# io.net
KiCad netlist of a schematic drawn in EAGLE
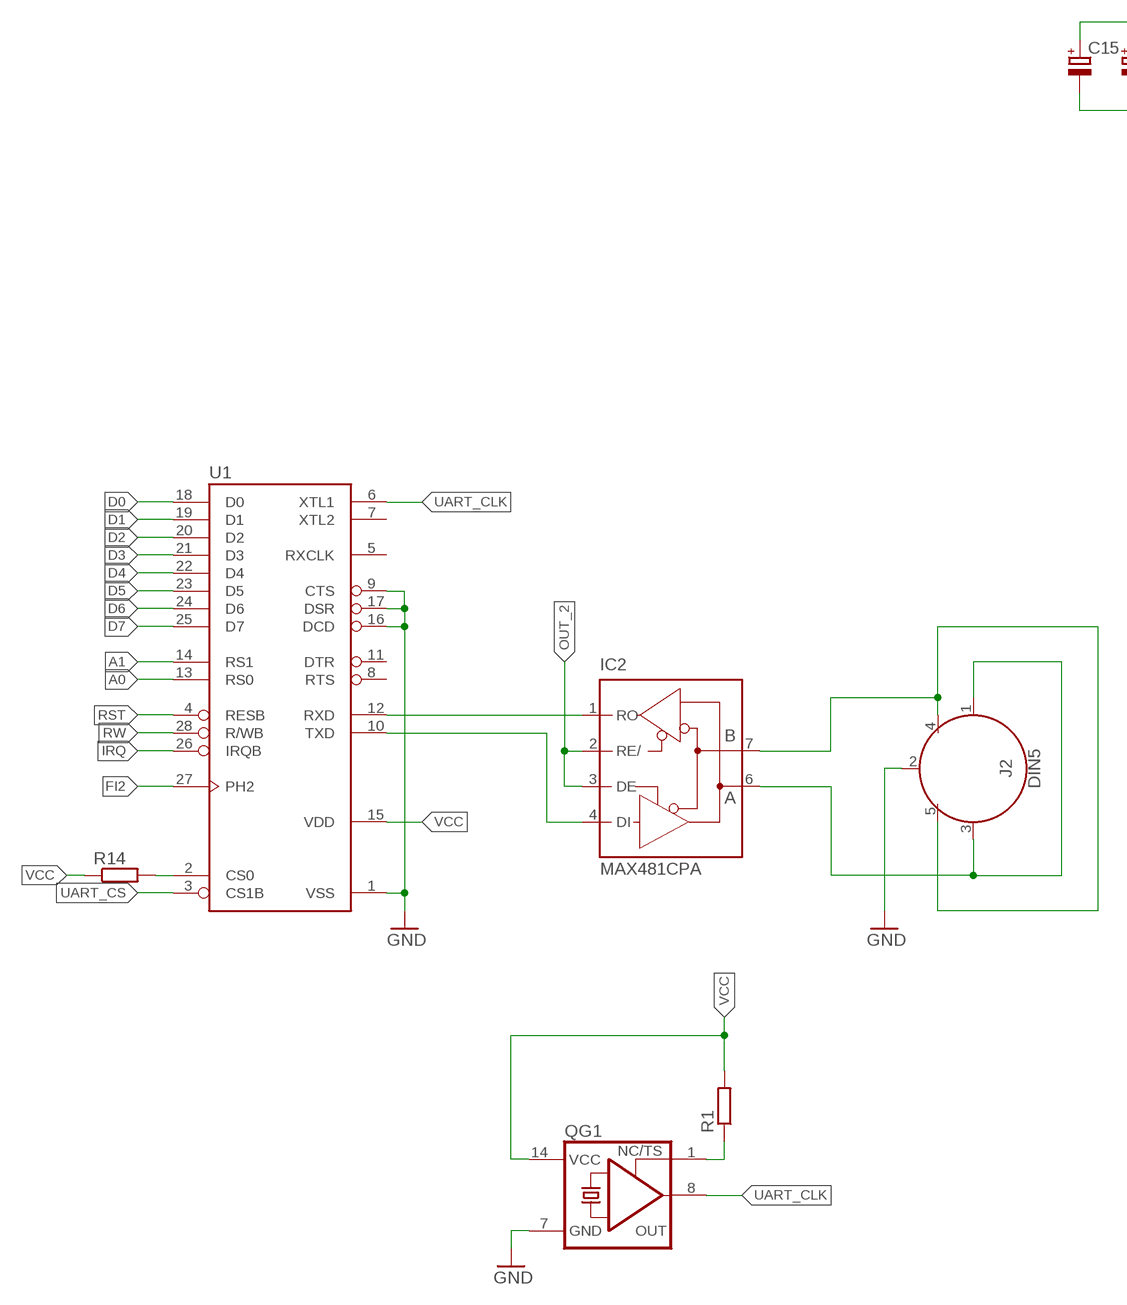
[diagram p0: schematic, sheet 1, part 1 of 2]
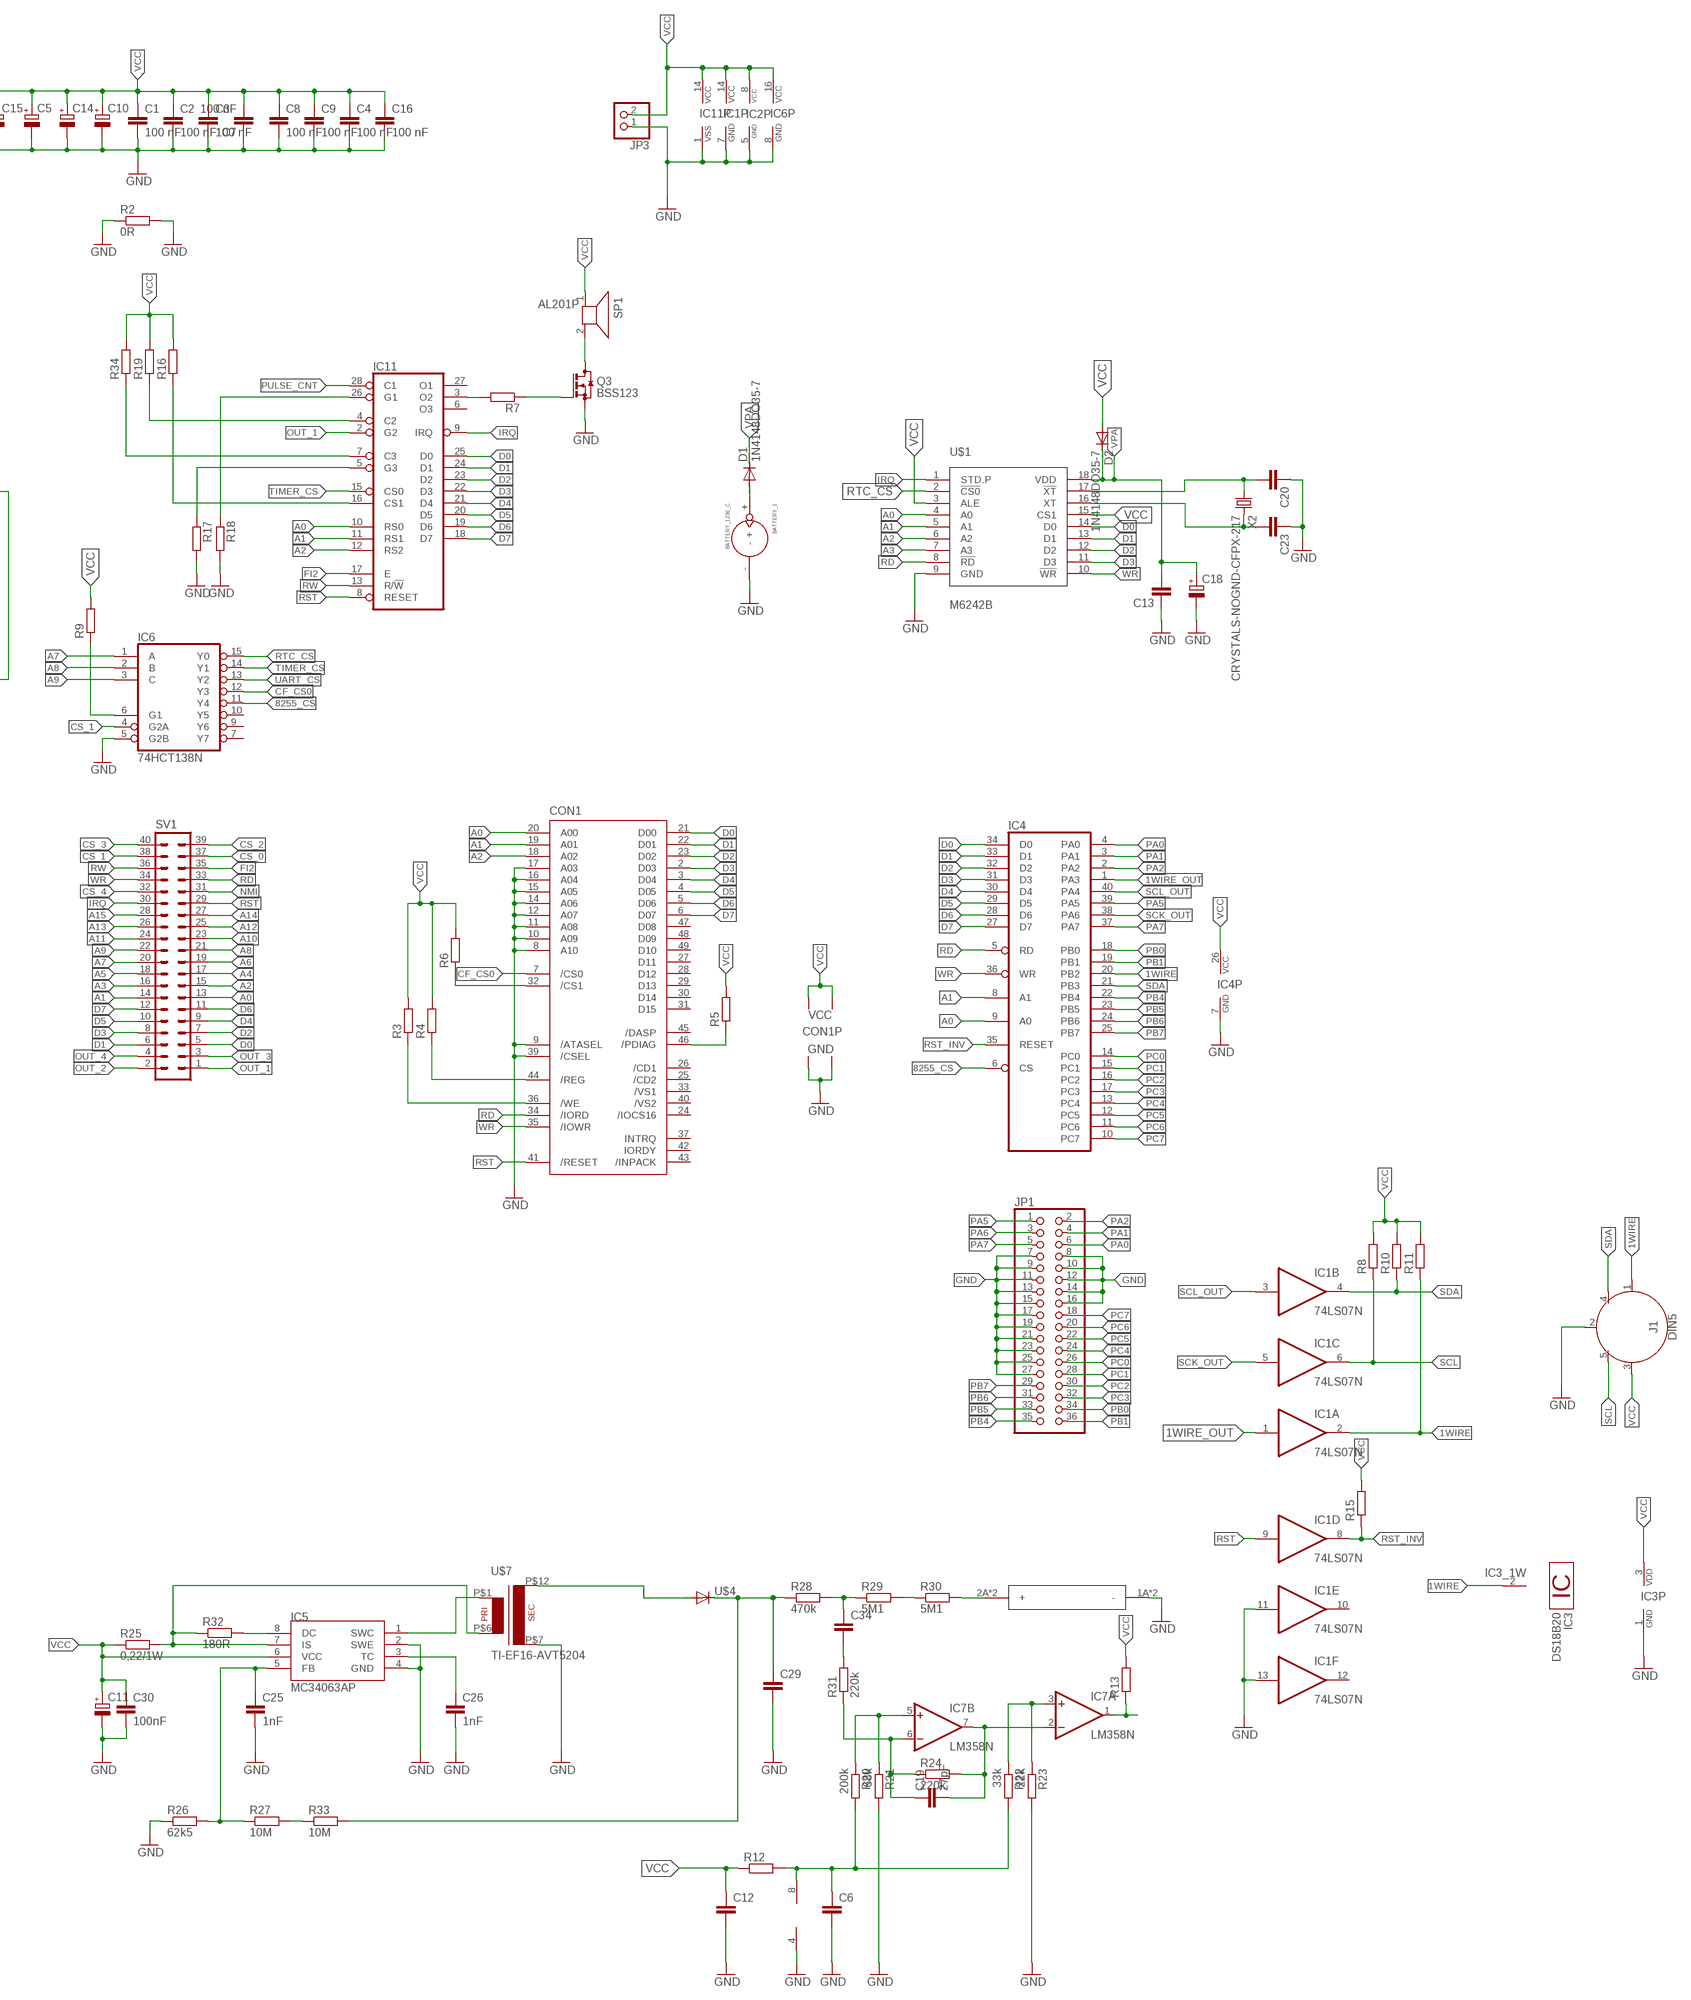
[diagram p1: schematic, sheet 1, part 2 of 2]

(export (version "E")
  (design (tool "Eeschema 10.0.6"))
  (components
    (comp (ref "BATTERY_1")
      (value "BATTERY_1236_C")
      (footprint "eagle-import:BATTERY_1236_C")
      (libsource (lib "eagle-import") (part "BATTERY_1236_C"))
    )
    (comp (ref "C1")
      (value "100 nF")
      (footprint "eagle-import:C1206")
      (libsource (lib "eagle-import") (part "C-EUC1206"))
    )
    (comp (ref "C2")
      (value "100 nF")
      (footprint "eagle-import:C1206")
      (libsource (lib "eagle-import") (part "C-EUC1206"))
    )
    (comp (ref "C3")
      (value "100 nF")
      (footprint "eagle-import:C1206")
      (libsource (lib "eagle-import") (part "C-EUC1206"))
    )
    (comp (ref "C4")
      (value "100 nF")
      (footprint "eagle-import:C0603")
      (libsource (lib "eagle-import") (part "C-EUC0603"))
    )
    (comp (ref "C5")
      (value "CPOL-EUSMCC")
      (footprint "eagle-import:SMC_C")
      (libsource (lib "eagle-import") (part "CPOL-EUSMCC"))
    )
    (comp (ref "C6")
      (value "C-EUC0603")
      (footprint "eagle-import:C0603")
      (libsource (lib "eagle-import") (part "C-EUC0603"))
    )
    (comp (ref "C7")
      (value "100 nF")
      (footprint "eagle-import:C0603")
      (libsource (lib "eagle-import") (part "C-EUC0603"))
    )
    (comp (ref "C8")
      (value "100 nF")
      (footprint "eagle-import:C1206")
      (libsource (lib "eagle-import") (part "C-EUC1206"))
    )
    (comp (ref "C9")
      (value "100 nF")
      (footprint "eagle-import:C1206")
      (libsource (lib "eagle-import") (part "C-EUC1206"))
    )
    (comp (ref "C10")
      (value "CPOL-EUE5-10.5")
      (footprint "eagle-import:E5-10,5")
      (libsource (lib "eagle-import") (part "CPOL-EUE5-10.5"))
    )
    (comp (ref "C11")
      (value "CPOL-EUSMCE")
      (footprint "eagle-import:SMC_E")
      (libsource (lib "eagle-import") (part "CPOL-EUSMCE"))
    )
    (comp (ref "C12")
      (value "C-EUC0603")
      (footprint "eagle-import:C0603")
      (libsource (lib "eagle-import") (part "C-EUC0603"))
    )
    (comp (ref "C13")
      (value "C-EUC0603")
      (footprint "eagle-import:C0603")
      (libsource (lib "eagle-import") (part "C-EUC0603"))
    )
    (comp (ref "C14")
      (value "CPOL-EUE3.5-8")
      (footprint "eagle-import:E3,5-8")
      (libsource (lib "eagle-import") (part "CPOL-EUE3.5-8"))
    )
    (comp (ref "C15")
      (value "CPOL-EUE5-10.5")
      (footprint "eagle-import:E5-10,5")
      (libsource (lib "eagle-import") (part "CPOL-EUE5-10.5"))
    )
    (comp (ref "C16")
      (value "100 nF")
      (footprint "eagle-import:C0603")
      (libsource (lib "eagle-import") (part "C-EUC0603"))
    )
    (comp (ref "C18")
      (value "CPOL-EUSMCB")
      (footprint "eagle-import:SMC_B")
      (libsource (lib "eagle-import") (part "CPOL-EUSMCB"))
    )
    (comp (ref "C19")
      (value "27pF")
      (footprint "eagle-import:C0603")
      (libsource (lib "eagle-import") (part "C-EUC0603"))
    )
    (comp (ref "C20")
      (value "C-EUC0603")
      (footprint "eagle-import:C0603")
      (libsource (lib "eagle-import") (part "C-EUC0603"))
    )
    (comp (ref "C23")
      (value "C-EUC0603")
      (footprint "eagle-import:C0603")
      (libsource (lib "eagle-import") (part "C-EUC0603"))
    )
    (comp (ref "C25")
      (value "1nF")
      (footprint "eagle-import:C0603")
      (libsource (lib "eagle-import") (part "C-EUC0603"))
    )
    (comp (ref "C26")
      (value "1nF")
      (footprint "eagle-import:C0603")
      (libsource (lib "eagle-import") (part "C-EUC0603"))
    )
    (comp (ref "C29")
      (value "C-EU225-113X268")
      (footprint "eagle-import:C225-113X268")
      (libsource (lib "eagle-import") (part "C-EU225-113X268"))
    )
    (comp (ref "C30")
      (value "100nF")
      (footprint "eagle-import:C0603")
      (libsource (lib "eagle-import") (part "C-EUC0603"))
    )
    (comp (ref "C34")
      (value "C-EU050-024X044")
      (footprint "eagle-import:C050-024X044")
      (libsource (lib "eagle-import") (part "C-EU050-024X044"))
    )
    (comp (ref "CON1")
      (value "CF-CARD-IDE_MODE")
      (footprint "eagle-import:MI20-50PD-SF")
      (libsource (lib "eagle-import") (part "CF-CARD-IDE_MODE"))
    )
    (comp (ref "D1")
      (value "1N4148DO35-7")
      (footprint "eagle-import:DO35-7")
      (libsource (lib "eagle-import") (part "1N4148DO35-7"))
    )
    (comp (ref "D2")
      (value "1N4148DO35-7")
      (footprint "eagle-import:DO35-7")
      (libsource (lib "eagle-import") (part "1N4148DO35-7"))
    )
    (comp (ref "IC1")
      (value "74LS07N")
      (footprint "eagle-import:DIL14")
      (libsource (lib "eagle-import") (part "7407NLS"))
    )
    (comp (ref "IC2")
      (value "MAX481CPA")
      (footprint "eagle-import:DIL08")
      (fields (field (name "MPN") "MAX481CPA+"))
      (libsource (lib "eagle-import") (part "MAX481CPA"))
    )
    (comp (ref "IC3")
      (value "DS18B20")
      (footprint "eagle-import:TO92-")
      (libsource (lib "eagle-import") (part "DS18B20"))
    )
    (comp (ref "IC4")
      (value "8255A")
      (footprint "eagle-import:DIL40")
      (libsource (lib "eagle-import") (part "8255A"))
    )
    (comp (ref "IC5")
      (value "MC34063AP")
      (footprint "eagle-import:DIL08")
      (libsource (lib "eagle-import") (part "MC34063AP"))
    )
    (comp (ref "IC6")
      (value "74HCT138N")
      (footprint "eagle-import:DIL16")
      (libsource (lib "eagle-import") (part "74138NHCT"))
    )
    (comp (ref "IC7")
      (value "LM358N")
      (footprint "eagle-import:DIL08")
      (libsource (lib "eagle-import") (part "LM358N"))
    )
    (comp (ref "IC11")
      (value "6840")
      (footprint "eagle-import:DIL28")
      (libsource (lib "eagle-import") (part "6840"))
    )
    (comp (ref "J1")
      (value "DIN5")
      (footprint "eagle-import:DIN5-RA-PTH")
      (libsource (lib "eagle-import") (part "DIN5"))
    )
    (comp (ref "J2")
      (value "DIN5")
      (footprint "eagle-import:DIN5-RA-PTH")
      (libsource (lib "eagle-import") (part "DIN5"))
    )
    (comp (ref "JP1")
      (value "PINHD-2X18")
      (footprint "eagle-import:2X18")
      (libsource (lib "eagle-import") (part "PINHD-2X18"))
    )
    (comp (ref "JP3")
      (value "PINHD-1X2/90")
      (footprint "eagle-import:1X02_90")
      (libsource (lib "eagle-import") (part "PINHD-1X2/90"))
    )
    (comp (ref "Q3")
      (value "BSS123")
      (footprint "eagle-import:SOT23")
      (libsource (lib "eagle-import") (part "BSS123"))
    )
    (comp (ref "QG1")
      (value "XO-14")
      (footprint "eagle-import:DIL14S")
      (libsource (lib "eagle-import") (part "XO-14"))
    )
    (comp (ref "R1")
      (value "R-EU_R1206")
      (footprint "eagle-import:R1206")
      (libsource (lib "eagle-import") (part "R-EU_R1206"))
    )
    (comp (ref "R2")
      (value "0R")
      (footprint "eagle-import:M1206")
      (libsource (lib "eagle-import") (part "R-EU_M1206"))
    )
    (comp (ref "R3")
      (value "R-EU_R0603")
      (footprint "eagle-import:R0603")
      (libsource (lib "eagle-import") (part "R-EU_R0603"))
    )
    (comp (ref "R4")
      (value "R-EU_R0603")
      (footprint "eagle-import:R0603")
      (libsource (lib "eagle-import") (part "R-EU_R0603"))
    )
    (comp (ref "R5")
      (value "R-EU_R0603")
      (footprint "eagle-import:R0603")
      (libsource (lib "eagle-import") (part "R-EU_R0603"))
    )
    (comp (ref "R6")
      (value "R-EU_R0603")
      (footprint "eagle-import:R0603")
      (libsource (lib "eagle-import") (part "R-EU_R0603"))
    )
    (comp (ref "R7")
      (value "R-EU_0204/5")
      (footprint "eagle-import:0204_5")
      (libsource (lib "eagle-import") (part "R-EU_0204/5"))
    )
    (comp (ref "R8")
      (value "R-EU_0204/7")
      (footprint "eagle-import:0204_7")
      (libsource (lib "eagle-import") (part "R-EU_0204/7"))
    )
    (comp (ref "R9")
      (value "R-EU_R1206")
      (footprint "eagle-import:R1206")
      (libsource (lib "eagle-import") (part "R-EU_R1206"))
    )
    (comp (ref "R10")
      (value "R-EU_0204/7")
      (footprint "eagle-import:0204_7")
      (libsource (lib "eagle-import") (part "R-EU_0204/7"))
    )
    (comp (ref "R11")
      (value "R-EU_0204/7")
      (footprint "eagle-import:0204_7")
      (libsource (lib "eagle-import") (part "R-EU_0204/7"))
    )
    (comp (ref "R12")
      (value "R-EU_0204/7")
      (footprint "eagle-import:0204_7")
      (libsource (lib "eagle-import") (part "R-EU_0204/7"))
    )
    (comp (ref "R13")
      (value "R-EU_R0603")
      (footprint "eagle-import:R0603")
      (libsource (lib "eagle-import") (part "R-EU_R0603"))
    )
    (comp (ref "R14")
      (value "R-EU_R0603")
      (footprint "eagle-import:R0603")
      (libsource (lib "eagle-import") (part "R-EU_R0603"))
    )
    (comp (ref "R15")
      (value "R-EU_R0603")
      (footprint "eagle-import:R0603")
      (libsource (lib "eagle-import") (part "R-EU_R0603"))
    )
    (comp (ref "R16")
      (value "R-EU_R0402")
      (footprint "eagle-import:R0402")
      (libsource (lib "eagle-import") (part "R-EU_R0402"))
    )
    (comp (ref "R17")
      (value "R-EU_0204/7")
      (footprint "eagle-import:0204_7")
      (libsource (lib "eagle-import") (part "R-EU_0204/7"))
    )
    (comp (ref "R18")
      (value "R-EU_R0603")
      (footprint "eagle-import:R0603")
      (libsource (lib "eagle-import") (part "R-EU_R0603"))
    )
    (comp (ref "R19")
      (value "R-EU_0204/5")
      (footprint "eagle-import:0204_5")
      (libsource (lib "eagle-import") (part "R-EU_0204/5"))
    )
    (comp (ref "R20")
      (value "200k")
      (footprint "eagle-import:R0603")
      (libsource (lib "eagle-import") (part "R-EU_R0603"))
    )
    (comp (ref "R21")
      (value "68k")
      (footprint "eagle-import:R0603")
      (libsource (lib "eagle-import") (part "R-EU_R0603"))
    )
    (comp (ref "R22")
      (value "33k")
      (footprint "eagle-import:R0603")
      (libsource (lib "eagle-import") (part "R-EU_R0603"))
    )
    (comp (ref "R23")
      (value "22k")
      (footprint "eagle-import:R0603")
      (libsource (lib "eagle-import") (part "R-EU_R0603"))
    )
    (comp (ref "R24")
      (value "220k")
      (footprint "eagle-import:R0603")
      (libsource (lib "eagle-import") (part "R-EU_R0603"))
    )
    (comp (ref "R25")
      (value "0,22/1W")
      (footprint "eagle-import:R2010")
      (libsource (lib "eagle-import") (part "R-EU_R2010"))
    )
    (comp (ref "R26")
      (value "62k5")
      (footprint "eagle-import:R1206")
      (libsource (lib "eagle-import") (part "R-EU_R1206"))
    )
    (comp (ref "R27")
      (value "10M")
      (footprint "eagle-import:0204_7")
      (libsource (lib "eagle-import") (part "R-EU_0204/7"))
    )
    (comp (ref "R28")
      (value "470k")
      (footprint "eagle-import:R2512")
      (libsource (lib "eagle-import") (part "R-EU_R2512"))
    )
    (comp (ref "R29")
      (value "5M1")
      (footprint "eagle-import:R2512")
      (libsource (lib "eagle-import") (part "R-EU_R2512"))
    )
    (comp (ref "R30")
      (value "5M1")
      (footprint "eagle-import:R2512")
      (libsource (lib "eagle-import") (part "R-EU_R2512"))
    )
    (comp (ref "R31")
      (value "220k")
      (footprint "eagle-import:0204_7")
      (libsource (lib "eagle-import") (part "R-EU_0204/7"))
    )
    (comp (ref "R32")
      (value "180R")
      (footprint "eagle-import:R0805")
      (libsource (lib "eagle-import") (part "R-EU_R0805"))
    )
    (comp (ref "R33")
      (value "10M")
      (footprint "eagle-import:0204_7")
      (libsource (lib "eagle-import") (part "R-EU_0204/7"))
    )
    (comp (ref "R34")
      (value "R-EU_R0603")
      (footprint "eagle-import:R0603")
      (libsource (lib "eagle-import") (part "R-EU_R0603"))
    )
    (comp (ref "SP1")
      (value "AL201P")
      (footprint "eagle-import:AL201P")
      (libsource (lib "eagle-import") (part "AL201P"))
    )
    (comp (ref "SV1")
      (value "ML40L")
      (footprint "eagle-import:ML40L")
      (libsource (lib "eagle-import") (part "ML40L"))
    )
    (comp (ref "U$1")
      (value "M6242B")
      (footprint "eagle-import:DIL18")
      (libsource (lib "eagle-import") (part "M6242B"))
    )
    (comp (ref "U$4")
      (value "DIODE-MELF-MLL41")
      (footprint "eagle-import:MELF-MLL41")
      (libsource (lib "eagle-import") (part "DIODE-MELF-MLL41"))
    )
    (comp (ref "U$5")
      (value "STS5")
      (footprint "eagle-import:GEIGERTUBE")
      (libsource (lib "eagle-import") (part "STS5"))
    )
    (comp (ref "U$7")
      (value "TI-EF16-AVT5204")
      (footprint "eagle-import:EF16-K-H-12P-12,5")
      (libsource (lib "eagle-import") (part "TI-EF16-AVT5204"))
    )
    (comp (ref "U1")
      (value "G65SC51P")
      (footprint "eagle-import:DIP-28")
      (libsource (lib "eagle-import") (part "G65SC51P"))
    )
    (comp (ref "X2")
      (value "CRYSTALS-NOGND-CFPX-217")
      (footprint "eagle-import:3.2X1.5-2-PAD")
      (libsource (lib "eagle-import") (part "CRYSTALS-NOGND-CFPX-217"))
    )
  )
  (nets
    (net (code "1") (name "1WIRE") (class "Default")
      (node (ref "IC1") (pin "2") (pinfunction "O_2") (pintype "open_collector"))
      (node (ref "IC3") (pin "2") (pinfunction "1W_2") (pintype "power_in"))
      (node (ref "IC4") (pin "20") (pinfunction "PB2_20") (pintype "bidirectional"))
      (node (ref "J1") (pin "1") (pinfunction "1_1") (pintype "bidirectional"))
      (node (ref "R11") (pin "1") (pinfunction "1_1") (pintype "passive"))
    )
    (net (code "2") (name "1WIRE_OUT") (class "Default")
      (node (ref "IC1") (pin "1") (pinfunction "I_1") (pintype "input"))
      (node (ref "IC4") (pin "1") (pinfunction "PA3_1") (pintype "bidirectional"))
    )
    (net (code "3") (name "8255_CS") (class "Default")
      (node (ref "IC4") (pin "6") (pinfunction "CS_6") (pintype "input"))
      (node (ref "IC6") (pin "11") (pinfunction "Y4_11") (pintype "output"))
    )
    (net (code "4") (name "A0") (class "Default")
      (node (ref "CON1") (pin "20") (pinfunction "A00_20") (pintype "input"))
      (node (ref "IC11") (pin "10") (pinfunction "RS0_10") (pintype "input"))
      (node (ref "IC4") (pin "9") (pinfunction "A0_9") (pintype "input"))
      (node (ref "SV1") (pin "13") (pinfunction "13_13") (pintype "passive"))
      (node (ref "U$1") (pin "4") (pinfunction "A0_4") (pintype "bidirectional"))
      (node (ref "U1") (pin "13") (pinfunction "RS0_13") (pintype "input"))
    )
    (net (code "5") (name "A1") (class "Default")
      (node (ref "CON1") (pin "19") (pinfunction "A01_19") (pintype "input"))
      (node (ref "IC11") (pin "11") (pinfunction "RS1_11") (pintype "input"))
      (node (ref "IC4") (pin "8") (pinfunction "A1_8") (pintype "input"))
      (node (ref "SV1") (pin "14") (pinfunction "14_14") (pintype "passive"))
      (node (ref "U$1") (pin "5") (pinfunction "A1_5") (pintype "bidirectional"))
      (node (ref "U1") (pin "14") (pinfunction "RS1_14") (pintype "input"))
    )
    (net (code "6") (name "A2") (class "Default")
      (node (ref "CON1") (pin "18") (pinfunction "A02_18") (pintype "input"))
      (node (ref "IC11") (pin "12") (pinfunction "RS2_12") (pintype "input"))
      (node (ref "SV1") (pin "15") (pinfunction "15_15") (pintype "passive"))
      (node (ref "U$1") (pin "6") (pinfunction "A2_6") (pintype "bidirectional"))
    )
    (net (code "7") (name "A3") (class "Default")
      (node (ref "SV1") (pin "16") (pinfunction "16_16") (pintype "passive"))
      (node (ref "U$1") (pin "7") (pinfunction "A3_7") (pintype "bidirectional"))
    )
    (net (code "8") (name "A4") (class "Default")
      (node (ref "SV1") (pin "17") (pinfunction "17_17") (pintype "passive"))
    )
    (net (code "9") (name "A5") (class "Default")
      (node (ref "SV1") (pin "18") (pinfunction "18_18") (pintype "passive"))
    )
    (net (code "10") (name "A6") (class "Default")
      (node (ref "SV1") (pin "19") (pinfunction "19_19") (pintype "passive"))
    )
    (net (code "11") (name "A7") (class "Default")
      (node (ref "IC6") (pin "1") (pinfunction "A_1") (pintype "input"))
      (node (ref "SV1") (pin "20") (pinfunction "20_20") (pintype "passive"))
    )
    (net (code "12") (name "A8") (class "Default")
      (node (ref "IC6") (pin "2") (pinfunction "B_2") (pintype "input"))
      (node (ref "SV1") (pin "21") (pinfunction "21_21") (pintype "passive"))
    )
    (net (code "13") (name "A9") (class "Default")
      (node (ref "IC6") (pin "3") (pinfunction "C_3") (pintype "input"))
      (node (ref "SV1") (pin "22") (pinfunction "22_22") (pintype "passive"))
    )
    (net (code "14") (name "A10") (class "Default")
      (node (ref "SV1") (pin "23") (pinfunction "23_23") (pintype "passive"))
    )
    (net (code "15") (name "A11") (class "Default")
      (node (ref "SV1") (pin "24") (pinfunction "24_24") (pintype "passive"))
    )
    (net (code "16") (name "A12") (class "Default")
      (node (ref "SV1") (pin "25") (pinfunction "25_25") (pintype "passive"))
    )
    (net (code "17") (name "A13") (class "Default")
      (node (ref "SV1") (pin "26") (pinfunction "26_26") (pintype "passive"))
    )
    (net (code "18") (name "A14") (class "Default")
      (node (ref "SV1") (pin "27") (pinfunction "27_27") (pintype "passive"))
    )
    (net (code "19") (name "A15") (class "Default")
      (node (ref "SV1") (pin "28") (pinfunction "28_28") (pintype "passive"))
    )
    (net (code "20") (name "CF_CS0") (class "Default")
      (node (ref "CON1") (pin "7") (pinfunction "/CS0_7") (pintype "input"))
      (node (ref "IC6") (pin "12") (pinfunction "Y3_12") (pintype "output"))
    )
    (net (code "21") (name "CS_0") (class "Default")
      (node (ref "SV1") (pin "37") (pinfunction "37_37") (pintype "passive"))
    )
    (net (code "22") (name "CS_1") (class "Default")
      (node (ref "IC6") (pin "4") (pinfunction "G2A_4") (pintype "input"))
      (node (ref "SV1") (pin "38") (pinfunction "38_38") (pintype "passive"))
    )
    (net (code "23") (name "CS_2") (class "Default")
      (node (ref "SV1") (pin "39") (pinfunction "39_39") (pintype "passive"))
    )
    (net (code "24") (name "CS_3") (class "Default")
      (node (ref "SV1") (pin "40") (pinfunction "40_40") (pintype "passive"))
    )
    (net (code "25") (name "CS_4") (class "Default")
      (node (ref "SV1") (pin "32") (pinfunction "32_32") (pintype "passive"))
    )
    (net (code "26") (name "D0") (class "Default")
      (node (ref "CON1") (pin "21") (pinfunction "D00_21") (pintype "bidirectional"))
      (node (ref "IC11") (pin "25") (pinfunction "D0_25") (pintype "bidirectional"))
      (node (ref "IC4") (pin "34") (pinfunction "D0_34") (pintype "bidirectional"))
      (node (ref "SV1") (pin "5") (pinfunction "5_5") (pintype "passive"))
      (node (ref "U$1") (pin "14") (pinfunction "D0_14") (pintype "bidirectional"))
      (node (ref "U1") (pin "18") (pinfunction "D0_18") (pintype "bidirectional"))
    )
    (net (code "27") (name "D1") (class "Default")
      (node (ref "CON1") (pin "22") (pinfunction "D01_22") (pintype "bidirectional"))
      (node (ref "IC11") (pin "24") (pinfunction "D1_24") (pintype "bidirectional"))
      (node (ref "IC4") (pin "33") (pinfunction "D1_33") (pintype "bidirectional"))
      (node (ref "SV1") (pin "6") (pinfunction "6_6") (pintype "passive"))
      (node (ref "U$1") (pin "13") (pinfunction "D1_13") (pintype "bidirectional"))
      (node (ref "U1") (pin "19") (pinfunction "D1_19") (pintype "bidirectional"))
    )
    (net (code "28") (name "D2") (class "Default")
      (node (ref "CON1") (pin "23") (pinfunction "D02_23") (pintype "bidirectional"))
      (node (ref "IC11") (pin "23") (pinfunction "D2_23") (pintype "bidirectional"))
      (node (ref "IC4") (pin "32") (pinfunction "D2_32") (pintype "bidirectional"))
      (node (ref "SV1") (pin "7") (pinfunction "7_7") (pintype "passive"))
      (node (ref "U$1") (pin "12") (pinfunction "D2_12") (pintype "bidirectional"))
      (node (ref "U1") (pin "20") (pinfunction "D2_20") (pintype "bidirectional"))
    )
    (net (code "29") (name "D3") (class "Default")
      (node (ref "CON1") (pin "2") (pinfunction "D03_2") (pintype "bidirectional"))
      (node (ref "IC11") (pin "22") (pinfunction "D3_22") (pintype "bidirectional"))
      (node (ref "IC4") (pin "31") (pinfunction "D3_31") (pintype "bidirectional"))
      (node (ref "SV1") (pin "8") (pinfunction "8_8") (pintype "passive"))
      (node (ref "U$1") (pin "11") (pinfunction "D3_11") (pintype "bidirectional"))
      (node (ref "U1") (pin "21") (pinfunction "D3_21") (pintype "bidirectional"))
    )
    (net (code "30") (name "D4") (class "Default")
      (node (ref "CON1") (pin "3") (pinfunction "D04_3") (pintype "bidirectional"))
      (node (ref "IC11") (pin "21") (pinfunction "D4_21") (pintype "bidirectional"))
      (node (ref "IC4") (pin "30") (pinfunction "D4_30") (pintype "bidirectional"))
      (node (ref "SV1") (pin "9") (pinfunction "9_9") (pintype "passive"))
      (node (ref "U1") (pin "22") (pinfunction "D4_22") (pintype "bidirectional"))
    )
    (net (code "31") (name "D5") (class "Default")
      (node (ref "CON1") (pin "4") (pinfunction "D05_4") (pintype "bidirectional"))
      (node (ref "IC11") (pin "20") (pinfunction "D5_20") (pintype "bidirectional"))
      (node (ref "IC4") (pin "29") (pinfunction "D5_29") (pintype "bidirectional"))
      (node (ref "SV1") (pin "10") (pinfunction "10_10") (pintype "passive"))
      (node (ref "U1") (pin "23") (pinfunction "D5_23") (pintype "bidirectional"))
    )
    (net (code "32") (name "D6") (class "Default")
      (node (ref "CON1") (pin "5") (pinfunction "D06_5") (pintype "bidirectional"))
      (node (ref "IC11") (pin "19") (pinfunction "D6_19") (pintype "bidirectional"))
      (node (ref "IC4") (pin "28") (pinfunction "D6_28") (pintype "bidirectional"))
      (node (ref "SV1") (pin "11") (pinfunction "11_11") (pintype "passive"))
      (node (ref "U1") (pin "24") (pinfunction "D6_24") (pintype "bidirectional"))
    )
    (net (code "33") (name "D7") (class "Default")
      (node (ref "CON1") (pin "6") (pinfunction "D07_6") (pintype "bidirectional"))
      (node (ref "IC11") (pin "18") (pinfunction "D7_18") (pintype "bidirectional"))
      (node (ref "IC4") (pin "27") (pinfunction "D7_27") (pintype "bidirectional"))
      (node (ref "SV1") (pin "12") (pinfunction "12_12") (pintype "passive"))
      (node (ref "U1") (pin "25") (pinfunction "D7_25") (pintype "bidirectional"))
    )
    (net (code "34") (name "FI2") (class "Default")
      (node (ref "IC11") (pin "17") (pinfunction "E_17") (pintype "input"))
      (node (ref "SV1") (pin "35") (pinfunction "35_35") (pintype "passive"))
      (node (ref "U1") (pin "27") (pinfunction "PH2_27") (pintype "power_in"))
    )
    (net (code "35") (name "GND") (class "Default")
      (node (ref "BATTERY_1") (pin "-") (pinfunction "-_-") (pintype "bidirectional"))
      (node (ref "C1") (pin "2") (pinfunction "2_2") (pintype "passive"))
      (node (ref "C10") (pin "-") (pinfunction "-_-") (pintype "passive"))
      (node (ref "C11") (pin "-") (pinfunction "-_-") (pintype "passive"))
      (node (ref "C12") (pin "2") (pinfunction "2_2") (pintype "passive"))
      (node (ref "C13") (pin "1") (pinfunction "1_1") (pintype "passive"))
      (node (ref "C14") (pin "-") (pinfunction "-_-") (pintype "passive"))
      (node (ref "C15") (pin "-") (pinfunction "-_-") (pintype "passive"))
      (node (ref "C16") (pin "2") (pinfunction "2_2") (pintype "passive"))
      (node (ref "C18") (pin "-") (pinfunction "-_-") (pintype "passive"))
      (node (ref "C2") (pin "2") (pinfunction "2_2") (pintype "passive"))
      (node (ref "C20") (pin "1") (pinfunction "1_1") (pintype "passive"))
      (node (ref "C23") (pin "1") (pinfunction "1_1") (pintype "passive"))
      (node (ref "C25") (pin "2") (pinfunction "2_2") (pintype "passive"))
      (node (ref "C26") (pin "2") (pinfunction "2_2") (pintype "passive"))
      (node (ref "C29") (pin "2") (pinfunction "2_2") (pintype "passive"))
      (node (ref "C3") (pin "2") (pinfunction "2_2") (pintype "passive"))
      (node (ref "C30") (pin "2") (pinfunction "2_2") (pintype "passive"))
      (node (ref "C4") (pin "2") (pinfunction "2_2") (pintype "passive"))
      (node (ref "C5") (pin "-") (pinfunction "-_-") (pintype "passive"))
      (node (ref "C6") (pin "2") (pinfunction "2_2") (pintype "passive"))
      (node (ref "C7") (pin "1") (pinfunction "1_1") (pintype "passive"))
      (node (ref "C8") (pin "2") (pinfunction "2_2") (pintype "passive"))
      (node (ref "C9") (pin "2") (pinfunction "2_2") (pintype "passive"))
      (node (ref "CON1") (pin "1") (pinfunction "GND1_1") (pintype "power_in"))
      (node (ref "CON1") (pin "10") (pinfunction "A09_10") (pintype "input"))
      (node (ref "CON1") (pin "11") (pinfunction "A08_11") (pintype "input"))
      (node (ref "CON1") (pin "12") (pinfunction "A07_12") (pintype "input"))
      (node (ref "CON1") (pin "14") (pinfunction "A06_14") (pintype "input"))
      (node (ref "CON1") (pin "15") (pinfunction "A05_15") (pintype "input"))
      (node (ref "CON1") (pin "16") (pinfunction "A04_16") (pintype "input"))
      (node (ref "CON1") (pin "17") (pinfunction "A03_17") (pintype "input"))
      (node (ref "CON1") (pin "39") (pinfunction "/CSEL_39") (pintype "input"))
      (node (ref "CON1") (pin "50") (pinfunction "GND2_50") (pintype "power_in"))
      (node (ref "CON1") (pin "8") (pinfunction "A10_8") (pintype "input"))
      (node (ref "CON1") (pin "9") (pinfunction "/ATASEL_9") (pintype "input"))
      (node (ref "IC1") (pin "11") (pinfunction "I_11") (pintype "input"))
      (node (ref "IC1") (pin "13") (pinfunction "I_13") (pintype "input"))
      (node (ref "IC1") (pin "7") (pinfunction "GND_7") (pintype "power_in"))
      (node (ref "IC11") (pin "1") (pinfunction "VSS_1") (pintype "power_in"))
      (node (ref "IC2") (pin "5") (pinfunction "GND_5") (pintype "power_in"))
      (node (ref "IC3") (pin "1") (pinfunction "GND_1") (pintype "power_in"))
      (node (ref "IC4") (pin "7") (pinfunction "GND_7") (pintype "power_in"))
      (node (ref "IC5") (pin "2") (pinfunction "SWE_2") (pintype "passive"))
      (node (ref "IC5") (pin "4") (pinfunction "GND_4") (pintype "passive"))
      (node (ref "IC6") (pin "5") (pinfunction "G2B_5") (pintype "input"))
      (node (ref "IC6") (pin "8") (pinfunction "GND_8") (pintype "power_in"))
      (node (ref "IC7") (pin "4") (pinfunction "V-_4") (pintype "power_in"))
      (node (ref "J1") (pin "2") (pinfunction "2_2") (pintype "bidirectional"))
      (node (ref "J2") (pin "2") (pinfunction "2_2") (pintype "bidirectional"))
      (node (ref "JP1") (pin "10") (pinfunction "10_10") (pintype "passive"))
      (node (ref "JP1") (pin "11") (pinfunction "11_11") (pintype "passive"))
      (node (ref "JP1") (pin "12") (pinfunction "12_12") (pintype "passive"))
      (node (ref "JP1") (pin "13") (pinfunction "13_13") (pintype "passive"))
      (node (ref "JP1") (pin "14") (pinfunction "14_14") (pintype "passive"))
      (node (ref "JP1") (pin "15") (pinfunction "15_15") (pintype "passive"))
      (node (ref "JP1") (pin "16") (pinfunction "16_16") (pintype "passive"))
      (node (ref "JP1") (pin "17") (pinfunction "17_17") (pintype "passive"))
      (node (ref "JP1") (pin "19") (pinfunction "19_19") (pintype "passive"))
      (node (ref "JP1") (pin "21") (pinfunction "21_21") (pintype "passive"))
      (node (ref "JP1") (pin "23") (pinfunction "23_23") (pintype "passive"))
      (node (ref "JP1") (pin "25") (pinfunction "25_25") (pintype "passive"))
      (node (ref "JP1") (pin "27") (pinfunction "27_27") (pintype "passive"))
      (node (ref "JP1") (pin "7") (pinfunction "7_7") (pintype "passive"))
      (node (ref "JP1") (pin "8") (pinfunction "8_8") (pintype "passive"))
      (node (ref "JP1") (pin "9") (pinfunction "9_9") (pintype "passive"))
      (node (ref "JP3") (pin "1") (pinfunction "1_1") (pintype "passive"))
      (node (ref "Q3") (pin "2") (pinfunction "S_2") (pintype "passive"))
      (node (ref "QG1") (pin "7") (pinfunction "GND_7") (pintype "power_in"))
      (node (ref "R17") (pin "2") (pinfunction "2_2") (pintype "passive"))
      (node (ref "R18") (pin "2") (pinfunction "2_2") (pintype "passive"))
      (node (ref "R2") (pin "1") (pinfunction "1_1") (pintype "passive"))
      (node (ref "R2") (pin "2") (pinfunction "2_2") (pintype "passive"))
      (node (ref "R21") (pin "2") (pinfunction "2_2") (pintype "passive"))
      (node (ref "R23") (pin "2") (pinfunction "2_2") (pintype "passive"))
      (node (ref "R26") (pin "1") (pinfunction "1_1") (pintype "passive"))
      (node (ref "U$1") (pin "9") (pinfunction "GND_9") (pintype "bidirectional"))
      (node (ref "U$5") (pin "1A") (pinfunction "-_1A") (pintype "bidirectional"))
      (node (ref "U$5") (pin "1B") (pinfunction "-_1B") (pintype "bidirectional"))
      (node (ref "U$7") (pin "P$7") (pinfunction "P7_P$7") (pintype "passive"))
      (node (ref "U1") (pin "1") (pinfunction "VSS_1") (pintype "power_in"))
      (node (ref "U1") (pin "16") (pinfunction "DCD_16") (pintype "input"))
      (node (ref "U1") (pin "17") (pinfunction "DSR_17") (pintype "input"))
      (node (ref "U1") (pin "9") (pinfunction "CTS_9") (pintype "input"))
    )
    (net (code "36") (name "IRQ") (class "Default")
      (node (ref "IC11") (pin "9") (pinfunction "IRQ_9") (pintype "open_collector"))
      (node (ref "SV1") (pin "30") (pinfunction "30_30") (pintype "passive"))
      (node (ref "U$1") (pin "1") (pinfunction "STD.P_1") (pintype "bidirectional"))
      (node (ref "U1") (pin "26") (pinfunction "IRQB_26") (pintype "output"))
    )
    (net (code "37") (name "NMI") (class "Default")
      (node (ref "SV1") (pin "31") (pinfunction "31_31") (pintype "passive"))
    )
    (net (code "38") (name "Net-(BATTERY_1-Pad+)") (class "Default")
      (node (ref "BATTERY_1") (pin "+") (pinfunction "+_+") (pintype "bidirectional"))
      (node (ref "D1") (pin "A") (pinfunction "A_A") (pintype "passive"))
    )
    (net (code "39") (name "Net-(C29-Pad1)") (class "Default")
      (node (ref "C29") (pin "1") (pinfunction "1_1") (pintype "passive"))
      (node (ref "R28") (pin "1") (pinfunction "1_1") (pintype "passive"))
      (node (ref "R33") (pin "2") (pinfunction "2_2") (pintype "passive"))
      (node (ref "U$4") (pin "C") (pinfunction "C_C") (pintype "passive"))
    )
    (net (code "40") (name "Net-(C34-Pad1)") (class "Default")
      (node (ref "C34") (pin "1") (pinfunction "1_1") (pintype "passive"))
      (node (ref "R28") (pin "2") (pinfunction "2_2") (pintype "passive"))
      (node (ref "R29") (pin "1") (pinfunction "1_1") (pintype "passive"))
    )
    (net (code "41") (name "Net-(C34-Pad2)") (class "Default")
      (node (ref "C34") (pin "2") (pinfunction "2_2") (pintype "passive"))
      (node (ref "R31") (pin "2") (pinfunction "2_2") (pintype "passive"))
    )
    (net (code "42") (name "Net-(CON1A-{slash}CS1)") (class "Default")
      (node (ref "CON1") (pin "32") (pinfunction "/CS1_32") (pintype "input"))
      (node (ref "R6") (pin "1") (pinfunction "1_1") (pintype "passive"))
    )
    (net (code "43") (name "Net-(CON1A-{slash}PDIAG)") (class "Default")
      (node (ref "CON1") (pin "46") (pinfunction "/PDIAG_46") (pintype "bidirectional"))
      (node (ref "R5") (pin "1") (pinfunction "1_1") (pintype "passive"))
    )
    (net (code "44") (name "Net-(CON1A-{slash}REG)") (class "Default")
      (node (ref "CON1") (pin "44") (pinfunction "/REG_44") (pintype "input"))
      (node (ref "R4") (pin "1") (pinfunction "1_1") (pintype "passive"))
    )
    (net (code "45") (name "Net-(CON1A-{slash}WE)") (class "Default")
      (node (ref "CON1") (pin "36") (pinfunction "/WE_36") (pintype "input"))
      (node (ref "R3") (pin "1") (pinfunction "1_1") (pintype "passive"))
    )
    (net (code "46") (name "Net-(IC2A-A)") (class "Default")
      (node (ref "IC2") (pin "6") (pinfunction "A_6") (pintype "passive"))
      (node (ref "J2") (pin "1") (pinfunction "1_1") (pintype "bidirectional"))
      (node (ref "J2") (pin "3") (pinfunction "3_3") (pintype "bidirectional"))
    )
    (net (code "47") (name "Net-(IC2A-B)") (class "Default")
      (node (ref "IC2") (pin "7") (pinfunction "B_7") (pintype "passive"))
      (node (ref "J2") (pin "4") (pinfunction "4_4") (pintype "bidirectional"))
      (node (ref "J2") (pin "5") (pinfunction "5_5") (pintype "bidirectional"))
    )
    (net (code "48") (name "Net-(IC2A-DI)") (class "Default")
      (node (ref "IC2") (pin "4") (pinfunction "DI_4") (pintype "input"))
      (node (ref "U1") (pin "10") (pinfunction "TXD_10") (pintype "output"))
    )
    (net (code "49") (name "Net-(IC2A-RO)") (class "Default")
      (node (ref "IC2") (pin "1") (pinfunction "RO_1") (pintype "output"))
      (node (ref "U1") (pin "12") (pinfunction "RXD_12") (pintype "input"))
    )
    (net (code "50") (name "Net-(IC5-DC)") (class "Default")
      (node (ref "IC5") (pin "8") (pinfunction "DC_8") (pintype "passive"))
      (node (ref "R32") (pin "2") (pinfunction "2_2") (pintype "passive"))
    )
    (net (code "51") (name "Net-(IC5-FB)") (class "Default")
      (node (ref "C25") (pin "1") (pinfunction "1_1") (pintype "passive"))
      (node (ref "IC5") (pin "5") (pinfunction "FB_5") (pintype "passive"))
      (node (ref "R26") (pin "2") (pinfunction "2_2") (pintype "passive"))
      (node (ref "R27") (pin "1") (pinfunction "1_1") (pintype "passive"))
    )
    (net (code "52") (name "Net-(IC5-IS)") (class "Default")
      (node (ref "IC5") (pin "7") (pinfunction "IS_7") (pintype "passive"))
      (node (ref "R25") (pin "2") (pinfunction "2_2") (pintype "passive"))
      (node (ref "R32") (pin "1") (pinfunction "1_1") (pintype "passive"))
      (node (ref "U$7") (pin "P$6") (pinfunction "P6_P$6") (pintype "passive"))
    )
    (net (code "53") (name "Net-(IC5-SWC)") (class "Default")
      (node (ref "IC5") (pin "1") (pinfunction "SWC_1") (pintype "passive"))
      (node (ref "U$7") (pin "P$1") (pinfunction "P1_P$1") (pintype "passive"))
    )
    (net (code "54") (name "Net-(IC5-TC)") (class "Default")
      (node (ref "C26") (pin "1") (pinfunction "1_1") (pintype "passive"))
      (node (ref "IC5") (pin "3") (pinfunction "TC_3") (pintype "passive"))
    )
    (net (code "55") (name "Net-(IC6A-G1)") (class "Default")
      (node (ref "IC6") (pin "6") (pinfunction "G1_6") (pintype "input"))
      (node (ref "R9") (pin "1") (pinfunction "1_1") (pintype "passive"))
    )
    (net (code "56") (name "Net-(IC7A-+IN)") (class "Default")
      (node (ref "IC7") (pin "3") (pinfunction "+IN_3") (pintype "input"))
      (node (ref "R22") (pin "1") (pinfunction "1_1") (pintype "passive"))
      (node (ref "R23") (pin "1") (pinfunction "1_1") (pintype "passive"))
    )
    (net (code "57") (name "Net-(IC7A--IN)") (class "Default")
      (node (ref "C19") (pin "2") (pinfunction "2_2") (pintype "passive"))
      (node (ref "IC7") (pin "2") (pinfunction "-IN_2") (pintype "input"))
      (node (ref "IC7") (pin "7") (pinfunction "OUT_7") (pintype "output"))
      (node (ref "R24") (pin "2") (pinfunction "2_2") (pintype "passive"))
    )
    (net (code "58") (name "Net-(IC7B-+IN)") (class "Default")
      (node (ref "IC7") (pin "5") (pinfunction "+IN_5") (pintype "input"))
      (node (ref "R20") (pin "1") (pinfunction "1_1") (pintype "passive"))
      (node (ref "R21") (pin "1") (pinfunction "1_1") (pintype "passive"))
    )
    (net (code "59") (name "Net-(IC7B--IN)") (class "Default")
      (node (ref "C19") (pin "1") (pinfunction "1_1") (pintype "passive"))
      (node (ref "IC7") (pin "6") (pinfunction "-IN_6") (pintype "input"))
      (node (ref "R24") (pin "1") (pinfunction "1_1") (pintype "passive"))
      (node (ref "R31") (pin "1") (pinfunction "1_1") (pintype "passive"))
    )
    (net (code "60") (name "Net-(IC7C-V+)") (class "Default")
      (node (ref "C6") (pin "1") (pinfunction "1_1") (pintype "passive"))
      (node (ref "IC7") (pin "8") (pinfunction "V+_8") (pintype "power_in"))
      (node (ref "R12") (pin "2") (pinfunction "2_2") (pintype "passive"))
      (node (ref "R20") (pin "2") (pinfunction "2_2") (pintype "passive"))
      (node (ref "R22") (pin "2") (pinfunction "2_2") (pintype "passive"))
    )
    (net (code "61") (name "Net-(IC11A-C2)") (class "Default")
      (node (ref "IC11") (pin "4") (pinfunction "C2_4") (pintype "input"))
      (node (ref "R19") (pin "1") (pinfunction "1_1") (pintype "passive"))
    )
    (net (code "62") (name "Net-(IC11A-C3)") (class "Default")
      (node (ref "IC11") (pin "7") (pinfunction "C3_7") (pintype "input"))
      (node (ref "R34") (pin "1") (pinfunction "1_1") (pintype "passive"))
    )
    (net (code "63") (name "Net-(IC11A-CS1)") (class "Default")
      (node (ref "IC11") (pin "16") (pinfunction "CS1_16") (pintype "input"))
      (node (ref "R16") (pin "1") (pinfunction "1_1") (pintype "passive"))
    )
    (net (code "64") (name "Net-(IC11A-G1)") (class "Default")
      (node (ref "IC11") (pin "26") (pinfunction "G1_26") (pintype "input"))
      (node (ref "R18") (pin "1") (pinfunction "1_1") (pintype "passive"))
    )
    (net (code "65") (name "Net-(IC11A-G3)") (class "Default")
      (node (ref "IC11") (pin "5") (pinfunction "G3_5") (pintype "input"))
      (node (ref "R17") (pin "1") (pinfunction "1_1") (pintype "passive"))
    )
    (net (code "66") (name "Net-(IC11A-O2)") (class "Default")
      (node (ref "IC11") (pin "3") (pinfunction "O2_3") (pintype "output"))
      (node (ref "R7") (pin "2") (pinfunction "2_2") (pintype "passive"))
    )
    (net (code "67") (name "Net-(Q3-D)") (class "Default")
      (node (ref "Q3") (pin "3") (pinfunction "D_3") (pintype "passive"))
      (node (ref "SP1") (pin "2") (pinfunction "2_2") (pintype "passive"))
    )
    (net (code "68") (name "Net-(Q3-G)") (class "Default")
      (node (ref "Q3") (pin "1") (pinfunction "G_1") (pintype "passive"))
      (node (ref "R7") (pin "1") (pinfunction "1_1") (pintype "passive"))
    )
    (net (code "69") (name "Net-(QG1-TS)") (class "Default")
      (node (ref "QG1") (pin "1") (pinfunction "TS_1") (pintype "passive"))
      (node (ref "R1") (pin "1") (pinfunction "1_1") (pintype "passive"))
    )
    (net (code "70") (name "Net-(R27-Pad2)") (class "Default")
      (node (ref "R27") (pin "2") (pinfunction "2_2") (pintype "passive"))
      (node (ref "R33") (pin "1") (pinfunction "1_1") (pintype "passive"))
    )
    (net (code "71") (name "Net-(R29-Pad2)") (class "Default")
      (node (ref "R29") (pin "2") (pinfunction "2_2") (pintype "passive"))
      (node (ref "R30") (pin "1") (pinfunction "1_1") (pintype "passive"))
    )
    (net (code "72") (name "Net-(R30-Pad2)") (class "Default")
      (node (ref "R30") (pin "2") (pinfunction "2_2") (pintype "passive"))
      (node (ref "U$5") (pin "2A") (pinfunction "+_2A") (pintype "bidirectional"))
      (node (ref "U$5") (pin "2B") (pinfunction "+_2B") (pintype "bidirectional"))
    )
    (net (code "73") (name "Net-(U$1-XT)") (class "Default")
      (node (ref "C23") (pin "2") (pinfunction "2_2") (pintype "passive"))
      (node (ref "U$1") (pin "16") (pinfunction "XT_16") (pintype "bidirectional"))
      (node (ref "X2") (pin "2") (pinfunction "2_2") (pintype "passive"))
    )
    (net (code "74") (name "Net-(U$1-~{XT})") (class "Default")
      (node (ref "C20") (pin "2") (pinfunction "2_2") (pintype "passive"))
      (node (ref "U$1") (pin "17") (pinfunction "~{XT}_17") (pintype "bidirectional"))
      (node (ref "X2") (pin "1") (pinfunction "1_1") (pintype "passive"))
    )
    (net (code "75") (name "Net-(U$7-P12)") (class "Default")
      (node (ref "U$4") (pin "A") (pinfunction "A_A") (pintype "passive"))
      (node (ref "U$7") (pin "P$12") (pinfunction "P12_P$12") (pintype "passive"))
    )
    (net (code "76") (name "Net-(U1-CS0)") (class "Default")
      (node (ref "R14") (pin "2") (pinfunction "2_2") (pintype "passive"))
      (node (ref "U1") (pin "2") (pinfunction "CS0_2") (pintype "input"))
    )
    (net (code "77") (name "OUT_1") (class "Default")
      (node (ref "IC11") (pin "2") (pinfunction "G2_2") (pintype "input"))
      (node (ref "SV1") (pin "1") (pinfunction "1_1") (pintype "passive"))
    )
    (net (code "78") (name "OUT_2") (class "Default")
      (node (ref "IC2") (pin "2") (pinfunction "RE/_2") (pintype "input"))
      (node (ref "IC2") (pin "3") (pinfunction "DE_3") (pintype "input"))
      (node (ref "SV1") (pin "2") (pinfunction "2_2") (pintype "passive"))
    )
    (net (code "79") (name "OUT_3") (class "Default")
      (node (ref "SV1") (pin "3") (pinfunction "3_3") (pintype "passive"))
    )
    (net (code "80") (name "OUT_4") (class "Default")
      (node (ref "SV1") (pin "4") (pinfunction "4_4") (pintype "passive"))
    )
    (net (code "81") (name "PA0") (class "Default")
      (node (ref "IC4") (pin "4") (pinfunction "PA0_4") (pintype "bidirectional"))
      (node (ref "JP1") (pin "6") (pinfunction "6_6") (pintype "passive"))
    )
    (net (code "82") (name "PA1") (class "Default")
      (node (ref "IC4") (pin "3") (pinfunction "PA1_3") (pintype "bidirectional"))
      (node (ref "JP1") (pin "4") (pinfunction "4_4") (pintype "passive"))
    )
    (net (code "83") (name "PA2") (class "Default")
      (node (ref "IC4") (pin "2") (pinfunction "PA2_2") (pintype "bidirectional"))
      (node (ref "JP1") (pin "2") (pinfunction "2_2") (pintype "passive"))
    )
    (net (code "84") (name "PA5") (class "Default")
      (node (ref "IC4") (pin "39") (pinfunction "PA5_39") (pintype "bidirectional"))
      (node (ref "JP1") (pin "1") (pinfunction "1_1") (pintype "passive"))
    )
    (net (code "85") (name "PA6") (class "Default")
      (node (ref "JP1") (pin "3") (pinfunction "3_3") (pintype "passive"))
    )
    (net (code "86") (name "PA7") (class "Default")
      (node (ref "IC4") (pin "37") (pinfunction "PA7_37") (pintype "bidirectional"))
      (node (ref "JP1") (pin "5") (pinfunction "5_5") (pintype "passive"))
    )
    (net (code "87") (name "PB0") (class "Default")
      (node (ref "IC4") (pin "18") (pinfunction "PB0_18") (pintype "bidirectional"))
      (node (ref "JP1") (pin "34") (pinfunction "34_34") (pintype "passive"))
    )
    (net (code "88") (name "PB1") (class "Default")
      (node (ref "IC4") (pin "19") (pinfunction "PB1_19") (pintype "bidirectional"))
      (node (ref "JP1") (pin "36") (pinfunction "36_36") (pintype "passive"))
    )
    (net (code "89") (name "PB4") (class "Default")
      (node (ref "IC4") (pin "22") (pinfunction "PB4_22") (pintype "bidirectional"))
      (node (ref "JP1") (pin "35") (pinfunction "35_35") (pintype "passive"))
    )
    (net (code "90") (name "PB5") (class "Default")
      (node (ref "IC4") (pin "23") (pinfunction "PB5_23") (pintype "bidirectional"))
      (node (ref "JP1") (pin "33") (pinfunction "33_33") (pintype "passive"))
    )
    (net (code "91") (name "PB6") (class "Default")
      (node (ref "IC4") (pin "24") (pinfunction "PB6_24") (pintype "bidirectional"))
      (node (ref "JP1") (pin "31") (pinfunction "31_31") (pintype "passive"))
    )
    (net (code "92") (name "PB7") (class "Default")
      (node (ref "IC4") (pin "25") (pinfunction "PB7_25") (pintype "bidirectional"))
      (node (ref "JP1") (pin "29") (pinfunction "29_29") (pintype "passive"))
    )
    (net (code "93") (name "PC0") (class "Default")
      (node (ref "IC4") (pin "14") (pinfunction "PC0_14") (pintype "bidirectional"))
      (node (ref "JP1") (pin "26") (pinfunction "26_26") (pintype "passive"))
    )
    (net (code "94") (name "PC1") (class "Default")
      (node (ref "IC4") (pin "15") (pinfunction "PC1_15") (pintype "bidirectional"))
      (node (ref "JP1") (pin "28") (pinfunction "28_28") (pintype "passive"))
    )
    (net (code "95") (name "PC2") (class "Default")
      (node (ref "IC4") (pin "16") (pinfunction "PC2_16") (pintype "bidirectional"))
      (node (ref "JP1") (pin "30") (pinfunction "30_30") (pintype "passive"))
    )
    (net (code "96") (name "PC3") (class "Default")
      (node (ref "IC4") (pin "17") (pinfunction "PC3_17") (pintype "bidirectional"))
      (node (ref "JP1") (pin "32") (pinfunction "32_32") (pintype "passive"))
    )
    (net (code "97") (name "PC4") (class "Default")
      (node (ref "IC4") (pin "13") (pinfunction "PC4_13") (pintype "bidirectional"))
      (node (ref "JP1") (pin "24") (pinfunction "24_24") (pintype "passive"))
    )
    (net (code "98") (name "PC5") (class "Default")
      (node (ref "IC4") (pin "12") (pinfunction "PC5_12") (pintype "bidirectional"))
      (node (ref "JP1") (pin "22") (pinfunction "22_22") (pintype "passive"))
    )
    (net (code "99") (name "PC6") (class "Default")
      (node (ref "IC4") (pin "11") (pinfunction "PC6_11") (pintype "bidirectional"))
      (node (ref "JP1") (pin "20") (pinfunction "20_20") (pintype "passive"))
    )
    (net (code "100") (name "PC7") (class "Default")
      (node (ref "IC4") (pin "10") (pinfunction "PC7_10") (pintype "bidirectional"))
      (node (ref "JP1") (pin "18") (pinfunction "18_18") (pintype "passive"))
    )
    (net (code "101") (name "PULSE_CNT") (class "Default")
      (node (ref "IC11") (pin "28") (pinfunction "C1_28") (pintype "input"))
      (node (ref "IC7") (pin "1") (pinfunction "OUT_1") (pintype "output"))
      (node (ref "R13") (pin "1") (pinfunction "1_1") (pintype "passive"))
    )
    (net (code "102") (name "RD") (class "Default")
      (node (ref "CON1") (pin "34") (pinfunction "/IORD_34") (pintype "input"))
      (node (ref "IC4") (pin "5") (pinfunction "RD_5") (pintype "input"))
      (node (ref "SV1") (pin "33") (pinfunction "33_33") (pintype "passive"))
      (node (ref "U$1") (pin "8") (pinfunction "~{RD}_8") (pintype "bidirectional"))
    )
    (net (code "103") (name "RST") (class "Default")
      (node (ref "CON1") (pin "41") (pinfunction "/RESET_41") (pintype "input"))
      (node (ref "IC1") (pin "9") (pinfunction "I_9") (pintype "input"))
      (node (ref "IC11") (pin "8") (pinfunction "RESET_8") (pintype "input"))
      (node (ref "SV1") (pin "29") (pinfunction "29_29") (pintype "passive"))
      (node (ref "U1") (pin "4") (pinfunction "RESB_4") (pintype "input"))
    )
    (net (code "104") (name "RST_INV") (class "Default")
      (node (ref "IC1") (pin "8") (pinfunction "O_8") (pintype "open_collector"))
      (node (ref "IC4") (pin "35") (pinfunction "RESET_35") (pintype "input"))
      (node (ref "R15") (pin "1") (pinfunction "1_1") (pintype "passive"))
    )
    (net (code "105") (name "RTC_CS") (class "Default")
      (node (ref "IC6") (pin "15") (pinfunction "Y0_15") (pintype "output"))
      (node (ref "U$1") (pin "2") (pinfunction "~{CS0}_2") (pintype "bidirectional"))
    )
    (net (code "106") (name "RW") (class "Default")
      (node (ref "IC11") (pin "13") (pinfunction "R/~{W}_13") (pintype "input"))
      (node (ref "SV1") (pin "36") (pinfunction "36_36") (pintype "passive"))
      (node (ref "U1") (pin "28") (pinfunction "R/WB_28") (pintype "input"))
    )
    (net (code "107") (name "SCK_OUT") (class "Default")
      (node (ref "IC1") (pin "5") (pinfunction "I_5") (pintype "input"))
      (node (ref "IC4") (pin "38") (pinfunction "PA6_38") (pintype "bidirectional"))
    )
    (net (code "108") (name "SCL") (class "Default")
      (node (ref "IC1") (pin "6") (pinfunction "O_6") (pintype "open_collector"))
      (node (ref "J1") (pin "5") (pinfunction "5_5") (pintype "bidirectional"))
      (node (ref "R8") (pin "1") (pinfunction "1_1") (pintype "passive"))
    )
    (net (code "109") (name "SCL_OUT") (class "Default")
      (node (ref "IC1") (pin "3") (pinfunction "I_3") (pintype "input"))
      (node (ref "IC4") (pin "40") (pinfunction "PA4_40") (pintype "bidirectional"))
    )
    (net (code "110") (name "SDA") (class "Default")
      (node (ref "IC1") (pin "4") (pinfunction "O_4") (pintype "open_collector"))
      (node (ref "IC4") (pin "21") (pinfunction "PB3_21") (pintype "bidirectional"))
      (node (ref "J1") (pin "4") (pinfunction "4_4") (pintype "bidirectional"))
      (node (ref "R10") (pin "1") (pinfunction "1_1") (pintype "passive"))
    )
    (net (code "111") (name "TIMER_CS") (class "Default")
      (node (ref "IC11") (pin "15") (pinfunction "CS0_15") (pintype "input"))
      (node (ref "IC6") (pin "14") (pinfunction "Y1_14") (pintype "output"))
    )
    (net (code "112") (name "UART_CLK") (class "Default")
      (node (ref "QG1") (pin "8") (pinfunction "OUT_8") (pintype "output"))
      (node (ref "U1") (pin "6") (pinfunction "XTL1_6") (pintype "input"))
    )
    (net (code "113") (name "UART_CS") (class "Default")
      (node (ref "IC6") (pin "13") (pinfunction "Y2_13") (pintype "output"))
      (node (ref "U1") (pin "3") (pinfunction "CS1B_3") (pintype "input"))
    )
    (net (code "114") (name "VCC") (class "Default")
      (node (ref "C1") (pin "1") (pinfunction "1_1") (pintype "passive"))
      (node (ref "C10") (pin "+") (pinfunction "+_+") (pintype "passive"))
      (node (ref "C11") (pin "+") (pinfunction "+_+") (pintype "passive"))
      (node (ref "C12") (pin "1") (pinfunction "1_1") (pintype "passive"))
      (node (ref "C14") (pin "+") (pinfunction "+_+") (pintype "passive"))
      (node (ref "C15") (pin "+") (pinfunction "+_+") (pintype "passive"))
      (node (ref "C16") (pin "1") (pinfunction "1_1") (pintype "passive"))
      (node (ref "C2") (pin "1") (pinfunction "1_1") (pintype "passive"))
      (node (ref "C3") (pin "1") (pinfunction "1_1") (pintype "passive"))
      (node (ref "C30") (pin "1") (pinfunction "1_1") (pintype "passive"))
      (node (ref "C4") (pin "1") (pinfunction "1_1") (pintype "passive"))
      (node (ref "C5") (pin "+") (pinfunction "+_+") (pintype "passive"))
      (node (ref "C7") (pin "2") (pinfunction "2_2") (pintype "passive"))
      (node (ref "C8") (pin "1") (pinfunction "1_1") (pintype "passive"))
      (node (ref "C9") (pin "1") (pinfunction "1_1") (pintype "passive"))
      (node (ref "CON1") (pin "13") (pinfunction "VCC2_13") (pintype "power_in"))
      (node (ref "CON1") (pin "38") (pinfunction "VCC1_38") (pintype "power_in"))
      (node (ref "D2") (pin "A") (pinfunction "A_A") (pintype "passive"))
      (node (ref "IC1") (pin "14") (pinfunction "VCC_14") (pintype "power_in"))
      (node (ref "IC11") (pin "14") (pinfunction "VCC_14") (pintype "power_in"))
      (node (ref "IC2") (pin "8") (pinfunction "VCC_8") (pintype "power_in"))
      (node (ref "IC3") (pin "3") (pinfunction "VDD_3") (pintype "power_in"))
      (node (ref "IC4") (pin "26") (pinfunction "VCC_26") (pintype "power_in"))
      (node (ref "IC5") (pin "6") (pinfunction "VCC_6") (pintype "passive"))
      (node (ref "IC6") (pin "16") (pinfunction "VCC_16") (pintype "power_in"))
      (node (ref "J1") (pin "3") (pinfunction "3_3") (pintype "bidirectional"))
      (node (ref "JP3") (pin "2") (pinfunction "2_2") (pintype "passive"))
      (node (ref "QG1") (pin "14") (pinfunction "VCC_14") (pintype "power_in"))
      (node (ref "R1") (pin "2") (pinfunction "2_2") (pintype "passive"))
      (node (ref "R10") (pin "2") (pinfunction "2_2") (pintype "passive"))
      (node (ref "R11") (pin "2") (pinfunction "2_2") (pintype "passive"))
      (node (ref "R12") (pin "1") (pinfunction "1_1") (pintype "passive"))
      (node (ref "R13") (pin "2") (pinfunction "2_2") (pintype "passive"))
      (node (ref "R14") (pin "1") (pinfunction "1_1") (pintype "passive"))
      (node (ref "R15") (pin "2") (pinfunction "2_2") (pintype "passive"))
      (node (ref "R16") (pin "2") (pinfunction "2_2") (pintype "passive"))
      (node (ref "R19") (pin "2") (pinfunction "2_2") (pintype "passive"))
      (node (ref "R25") (pin "1") (pinfunction "1_1") (pintype "passive"))
      (node (ref "R3") (pin "2") (pinfunction "2_2") (pintype "passive"))
      (node (ref "R34") (pin "2") (pinfunction "2_2") (pintype "passive"))
      (node (ref "R4") (pin "2") (pinfunction "2_2") (pintype "passive"))
      (node (ref "R5") (pin "2") (pinfunction "2_2") (pintype "passive"))
      (node (ref "R6") (pin "2") (pinfunction "2_2") (pintype "passive"))
      (node (ref "R8") (pin "2") (pinfunction "2_2") (pintype "passive"))
      (node (ref "R9") (pin "2") (pinfunction "2_2") (pintype "passive"))
      (node (ref "SP1") (pin "1") (pinfunction "1_1") (pintype "passive"))
      (node (ref "U$1") (pin "15") (pinfunction "CS1_15") (pintype "bidirectional"))
      (node (ref "U$1") (pin "3") (pinfunction "ALE_3") (pintype "bidirectional"))
      (node (ref "U1") (pin "15") (pinfunction "VDD_15") (pintype "power_in"))
    )
    (net (code "115") (name "VPA") (class "Default")
      (node (ref "C13") (pin "2") (pinfunction "2_2") (pintype "passive"))
      (node (ref "C18") (pin "+") (pinfunction "+_+") (pintype "passive"))
      (node (ref "D1") (pin "C") (pinfunction "C_C") (pintype "passive"))
      (node (ref "D2") (pin "C") (pinfunction "C_C") (pintype "passive"))
      (node (ref "U$1") (pin "18") (pinfunction "VDD_18") (pintype "bidirectional"))
    )
    (net (code "116") (name "WR") (class "Default")
      (node (ref "CON1") (pin "35") (pinfunction "/IOWR_35") (pintype "input"))
      (node (ref "IC4") (pin "36") (pinfunction "WR_36") (pintype "input"))
      (node (ref "SV1") (pin "34") (pinfunction "34_34") (pintype "passive"))
      (node (ref "U$1") (pin "10") (pinfunction "~{WR}_10") (pintype "bidirectional"))
    )
    (net (code "117") (name "unconnected-(CON1A-D08-Pad47)") (class "Default")
      (node (ref "CON1") (pin "47") (pinfunction "D08_47") (pintype "bidirectional"))
    )
    (net (code "118") (name "unconnected-(CON1A-D09-Pad48)") (class "Default")
      (node (ref "CON1") (pin "48") (pinfunction "D09_48") (pintype "bidirectional"))
    )
    (net (code "119") (name "unconnected-(CON1A-D10-Pad49)") (class "Default")
      (node (ref "CON1") (pin "49") (pinfunction "D10_49") (pintype "bidirectional"))
    )
    (net (code "120") (name "unconnected-(CON1A-D11-Pad27)") (class "Default")
      (node (ref "CON1") (pin "27") (pinfunction "D11_27") (pintype "bidirectional"))
    )
    (net (code "121") (name "unconnected-(CON1A-D12-Pad28)") (class "Default")
      (node (ref "CON1") (pin "28") (pinfunction "D12_28") (pintype "bidirectional"))
    )
    (net (code "122") (name "unconnected-(CON1A-D13-Pad29)") (class "Default")
      (node (ref "CON1") (pin "29") (pinfunction "D13_29") (pintype "bidirectional"))
    )
    (net (code "123") (name "unconnected-(CON1A-D14-Pad30)") (class "Default")
      (node (ref "CON1") (pin "30") (pinfunction "D14_30") (pintype "bidirectional"))
    )
    (net (code "124") (name "unconnected-(CON1A-D15-Pad31)") (class "Default")
      (node (ref "CON1") (pin "31") (pinfunction "D15_31") (pintype "bidirectional"))
    )
    (net (code "125") (name "unconnected-(CON1A-INTRQ-Pad37)") (class "Default")
      (node (ref "CON1") (pin "37") (pinfunction "INTRQ_37") (pintype "output"))
    )
    (net (code "126") (name "unconnected-(CON1A-IORDY-Pad42)") (class "Default")
      (node (ref "CON1") (pin "42") (pinfunction "IORDY_42") (pintype "output"))
    )
    (net (code "127") (name "unconnected-(CON1A-{slash}CD1-Pad26)") (class "Default")
      (node (ref "CON1") (pin "26") (pinfunction "/CD1_26") (pintype "output"))
    )
    (net (code "128") (name "unconnected-(CON1A-{slash}CD2-Pad25)") (class "Default")
      (node (ref "CON1") (pin "25") (pinfunction "/CD2_25") (pintype "output"))
    )
    (net (code "129") (name "unconnected-(CON1A-{slash}DASP-Pad45)") (class "Default")
      (node (ref "CON1") (pin "45") (pinfunction "/DASP_45") (pintype "bidirectional"))
    )
    (net (code "130") (name "unconnected-(CON1A-{slash}INPACK-Pad43)") (class "Default")
      (node (ref "CON1") (pin "43") (pinfunction "/INPACK_43") (pintype "output"))
    )
    (net (code "131") (name "unconnected-(CON1A-{slash}IOCS16-Pad24)") (class "Default")
      (node (ref "CON1") (pin "24") (pinfunction "/IOCS16_24") (pintype "output"))
    )
    (net (code "132") (name "unconnected-(CON1A-{slash}VS1-Pad33)") (class "Default")
      (node (ref "CON1") (pin "33") (pinfunction "/VS1_33") (pintype "output"))
    )
    (net (code "133") (name "unconnected-(CON1A-{slash}VS2-Pad40)") (class "Default")
      (node (ref "CON1") (pin "40") (pinfunction "/VS2_40") (pintype "output"))
    )
    (net (code "134") (name "unconnected-(IC1E-O-Pad10)") (class "Default")
      (node (ref "IC1") (pin "10") (pinfunction "O_10") (pintype "open_collector"))
    )
    (net (code "135") (name "unconnected-(IC1F-O-Pad12)") (class "Default")
      (node (ref "IC1") (pin "12") (pinfunction "O_12") (pintype "open_collector"))
    )
    (net (code "136") (name "unconnected-(IC6A-Y5-Pad10)") (class "Default")
      (node (ref "IC6") (pin "10") (pinfunction "Y5_10") (pintype "output"))
    )
    (net (code "137") (name "unconnected-(IC6A-Y6-Pad9)") (class "Default")
      (node (ref "IC6") (pin "9") (pinfunction "Y6_9") (pintype "output"))
    )
    (net (code "138") (name "unconnected-(IC6A-Y7-Pad7)") (class "Default")
      (node (ref "IC6") (pin "7") (pinfunction "Y7_7") (pintype "output"))
    )
    (net (code "139") (name "unconnected-(IC11A-O1-Pad27)") (class "Default")
      (node (ref "IC11") (pin "27") (pinfunction "O1_27") (pintype "output"))
    )
    (net (code "140") (name "unconnected-(IC11A-O3-Pad6)") (class "Default")
      (node (ref "IC11") (pin "6") (pinfunction "O3_6") (pintype "output"))
    )
    (net (code "141") (name "unconnected-(U1-DTR-Pad11)") (class "Default")
      (node (ref "U1") (pin "11") (pinfunction "DTR_11") (pintype "output"))
    )
    (net (code "142") (name "unconnected-(U1-RTS-Pad8)") (class "Default")
      (node (ref "U1") (pin "8") (pinfunction "RTS_8") (pintype "output"))
    )
    (net (code "143") (name "unconnected-(U1-RXCLK-Pad5)") (class "Default")
      (node (ref "U1") (pin "5") (pinfunction "RXCLK_5") (pintype "bidirectional"))
    )
    (net (code "144") (name "unconnected-(U1-XTL2-Pad7)") (class "Default")
      (node (ref "U1") (pin "7") (pinfunction "XTL2_7") (pintype "output"))
    )
  )
)
